# power_regulation.net
KiCad netlist of a schematic drawn in Altium Designer
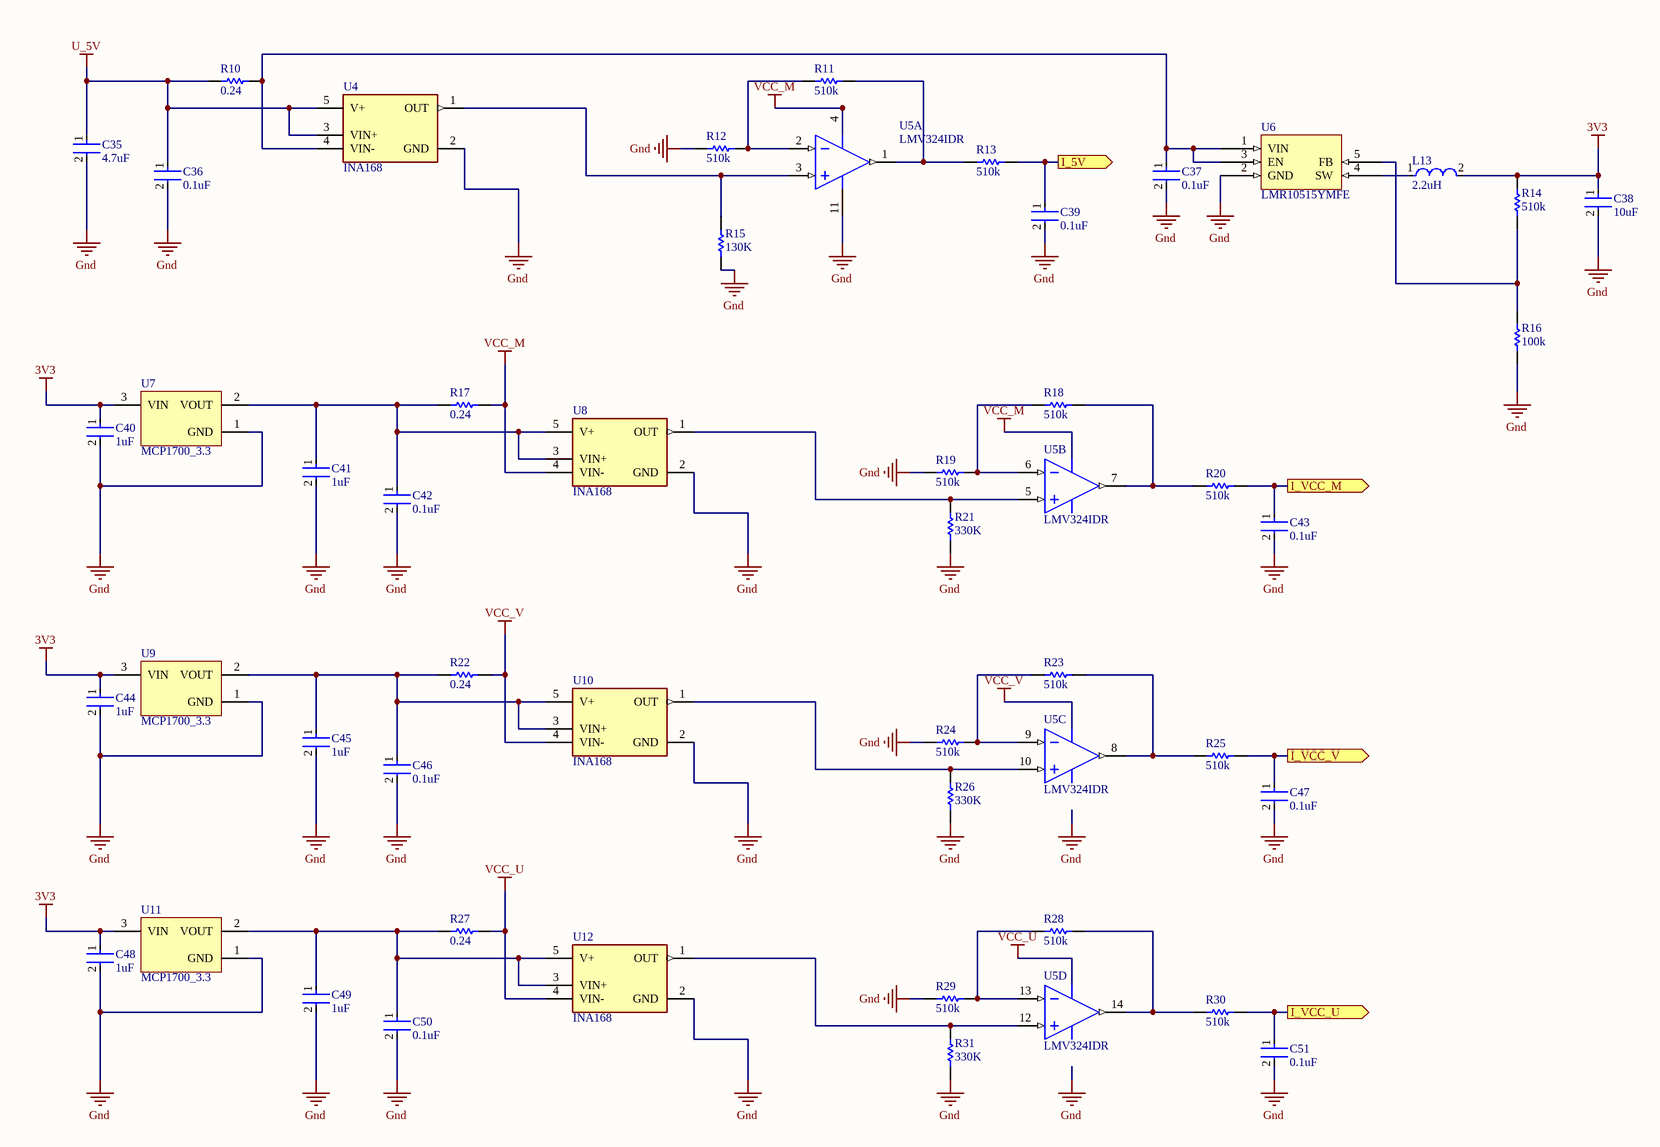
[diagram p0: power_regulation.SchDoc]

(export (version "E")
  (design (tool "Eeschema 10.0.6"))
  (components
    (comp (ref "C35")
      (value "4.7uF")
      (footprint "FP-C0805C-DN-IPC_A")
      (description "Cap Ceramic 4.7uF 25V X5R 10% SMD 0805 85°C Plastic T/R")
      (fields
        (field (name "MANUFACTURER") "KEMET")
        (field (name "MANUFACTURER PART NUMBER") "C0805C475K3PACTU")
      )
      (libsource (lib "WEST_Schematic_Library") (part "C0805C475K3PACTU"))
    )
    (comp (ref "C36")
      (value "0.1uF")
      (footprint "FP-C0805C-DN-IPC_A")
      (description "Cap Ceramic 0.1uF 50V X7R 10% SMD 2.0 x 1.2 mm 125 C Paper T/R")
      (fields
        (field (name "MANUFACTURER") "KEMET")
        (field (name "MANUFACTURER PART NUMBER") "C0805C104K5RACTU")
      )
      (libsource (lib "WEST_Schematic_Library") (part "C0805C104K5RACTU"))
    )
    (comp (ref "C37")
      (value "0.1uF")
      (footprint "FP-C0805C-DN-IPC_A")
      (description "Cap Ceramic 0.1uF 50V X7R 10% SMD 2.0 x 1.2 mm 125 C Paper T/R")
      (fields
        (field (name "MANUFACTURER") "KEMET")
        (field (name "MANUFACTURER PART NUMBER") "C0805C104K5RACTU")
      )
      (libsource (lib "WEST_Schematic_Library") (part "C0805C104K5RACTU"))
    )
    (comp (ref "C38")
      (value "10uF")
      (footprint "FP-C0805C-DN-IPC_A")
      (description "贴片电容（MLCC） 10μF ±10% 16V X5R 0805")
      (fields
        (field (name "MANUFACTURER") "Murata")
        (field (name "MANUFACTURER PART NUMBER") "GRM21BR61C106KE15L")
      )
      (libsource (lib "WEST_Schematic_Library") (part "GRM21BR61C106KE15L"))
    )
    (comp (ref "C39")
      (value "0.1uF")
      (footprint "FP-C0805C-DN-IPC_A")
      (description "Cap Ceramic 0.1uF 50V X7R 10% SMD 2.0 x 1.2 mm 125 C Paper T/R")
      (fields
        (field (name "MANUFACTURER") "KEMET")
        (field (name "MANUFACTURER PART NUMBER") "C0805C104K5RACTU")
      )
      (libsource (lib "WEST_Schematic_Library") (part "C0805C104K5RACTU"))
    )
    (comp (ref "C40")
      (value "1uF")
      (footprint "FP-C0805C-DN-IPC_A")
      (description "Cap Ceramic 1uF 16V X5R 10% SMD 0805 85C Plastic T/R")
      (fields
        (field (name "MANUFACTURER") "KEMET")
        (field (name "MANUFACTURER PART NUMBER") "C0805C105K4PACTU")
      )
      (libsource (lib "WEST_Schematic_Library") (part "C0805C105K4PACTU"))
    )
    (comp (ref "C41")
      (value "1uF")
      (footprint "FP-C0805C-DN-IPC_A")
      (description "Cap Ceramic 1uF 16V X5R 10% SMD 0805 85C Plastic T/R")
      (fields
        (field (name "MANUFACTURER") "KEMET")
        (field (name "MANUFACTURER PART NUMBER") "C0805C105K4PACTU")
      )
      (libsource (lib "WEST_Schematic_Library") (part "C0805C105K4PACTU"))
    )
    (comp (ref "C42")
      (value "0.1uF")
      (footprint "FP-C0805C-DN-IPC_A")
      (description "Cap Ceramic 0.1uF 50V X7R 10% SMD 2.0 x 1.2 mm 125 C Paper T/R")
      (fields
        (field (name "MANUFACTURER") "KEMET")
        (field (name "MANUFACTURER PART NUMBER") "C0805C104K5RACTU")
      )
      (libsource (lib "WEST_Schematic_Library") (part "C0805C104K5RACTU"))
    )
    (comp (ref "C43")
      (value "0.1uF")
      (footprint "FP-C0805C-DN-IPC_A")
      (description "Cap Ceramic 0.1uF 50V X7R 10% SMD 2.0 x 1.2 mm 125 C Paper T/R")
      (fields
        (field (name "MANUFACTURER") "KEMET")
        (field (name "MANUFACTURER PART NUMBER") "C0805C104K5RACTU")
      )
      (libsource (lib "WEST_Schematic_Library") (part "C0805C104K5RACTU"))
    )
    (comp (ref "C44")
      (value "1uF")
      (footprint "FP-C0805C-DN-IPC_A")
      (description "Cap Ceramic 1uF 16V X5R 10% SMD 0805 85C Plastic T/R")
      (fields
        (field (name "MANUFACTURER") "KEMET")
        (field (name "MANUFACTURER PART NUMBER") "C0805C105K4PACTU")
      )
      (libsource (lib "WEST_Schematic_Library") (part "C0805C105K4PACTU"))
    )
    (comp (ref "C45")
      (value "1uF")
      (footprint "FP-C0805C-DN-IPC_A")
      (description "Cap Ceramic 1uF 16V X5R 10% SMD 0805 85C Plastic T/R")
      (fields
        (field (name "MANUFACTURER") "KEMET")
        (field (name "MANUFACTURER PART NUMBER") "C0805C105K4PACTU")
      )
      (libsource (lib "WEST_Schematic_Library") (part "C0805C105K4PACTU"))
    )
    (comp (ref "C46")
      (value "0.1uF")
      (footprint "FP-C0805C-DN-IPC_A")
      (description "Cap Ceramic 0.1uF 50V X7R 10% SMD 2.0 x 1.2 mm 125 C Paper T/R")
      (fields
        (field (name "MANUFACTURER") "KEMET")
        (field (name "MANUFACTURER PART NUMBER") "C0805C104K5RACTU")
      )
      (libsource (lib "WEST_Schematic_Library") (part "C0805C104K5RACTU"))
    )
    (comp (ref "C47")
      (value "0.1uF")
      (footprint "FP-C0805C-DN-IPC_A")
      (description "Cap Ceramic 0.1uF 50V X7R 10% SMD 2.0 x 1.2 mm 125 C Paper T/R")
      (fields
        (field (name "MANUFACTURER") "KEMET")
        (field (name "MANUFACTURER PART NUMBER") "C0805C104K5RACTU")
      )
      (libsource (lib "WEST_Schematic_Library") (part "C0805C104K5RACTU"))
    )
    (comp (ref "C48")
      (value "1uF")
      (footprint "FP-C0805C-DN-IPC_A")
      (description "Cap Ceramic 1uF 16V X5R 10% SMD 0805 85C Plastic T/R")
      (fields
        (field (name "MANUFACTURER") "KEMET")
        (field (name "MANUFACTURER PART NUMBER") "C0805C105K4PACTU")
      )
      (libsource (lib "WEST_Schematic_Library") (part "C0805C105K4PACTU"))
    )
    (comp (ref "C49")
      (value "1uF")
      (footprint "FP-C0805C-DN-IPC_A")
      (description "Cap Ceramic 1uF 16V X5R 10% SMD 0805 85C Plastic T/R")
      (fields
        (field (name "MANUFACTURER") "KEMET")
        (field (name "MANUFACTURER PART NUMBER") "C0805C105K4PACTU")
      )
      (libsource (lib "WEST_Schematic_Library") (part "C0805C105K4PACTU"))
    )
    (comp (ref "C50")
      (value "0.1uF")
      (footprint "FP-C0805C-DN-IPC_A")
      (description "Cap Ceramic 0.1uF 50V X7R 10% SMD 2.0 x 1.2 mm 125 C Paper T/R")
      (fields
        (field (name "MANUFACTURER") "KEMET")
        (field (name "MANUFACTURER PART NUMBER") "C0805C104K5RACTU")
      )
      (libsource (lib "WEST_Schematic_Library") (part "C0805C104K5RACTU"))
    )
    (comp (ref "C51")
      (value "0.1uF")
      (footprint "FP-C0805C-DN-IPC_A")
      (description "Cap Ceramic 0.1uF 50V X7R 10% SMD 2.0 x 1.2 mm 125 C Paper T/R")
      (fields
        (field (name "MANUFACTURER") "KEMET")
        (field (name "MANUFACTURER PART NUMBER") "C0805C104K5RACTU")
      )
      (libsource (lib "WEST_Schematic_Library") (part "C0805C104K5RACTU"))
    )
    (comp (ref "L13")
      (value "2.2uH")
      (footprint "FP-C0805C-DN-IPC_A")
      (description "0805 2.2uH ±20% DCR=340mΩ 600mA SRF=50MHz")
      (fields
        (field (name "MANUFACTURER") "Murata")
        (field (name "MANUFACTURER PART NUMBER") "LQM21PN2R2MC0D")
      )
      (libsource (lib "WEST_Schematic_Library") (part "LQM21PN2R2MC0D"))
    )
    (comp (ref "R10")
      (value "0.24")
      (footprint "FP-C0805C-DN-IPC_A")
      (description "Res Thin Film 0805 0.24 Ohm 1% 0.33W(1/3W) 0ppm/C to 200ppm/C Pad SMD Automotive T/R")
      (fields
        (field (name "MANUFACTURER") "Susumu")
        (field (name "MANUFACTURER PART NUMBER") "RL1220S-R24-F")
      )
      (libsource (lib "WEST_Schematic_Library") (part "RL1220S-R24-F"))
    )
    (comp (ref "R11")
      (value "510k")
      (footprint "FP-C0805C-DN-IPC_A")
      (description "贴片电阻 510KΩ ±1% 1/8W ±100ppm/℃ 0805")
      (fields
        (field (name "MANUFACTURER") "Panasonic")
        (field (name "MANUFACTURER PART NUMBER") "ERJ6ENF5103V")
      )
      (libsource (lib "WEST_Schematic_Library") (part "ERJ6ENF5103V"))
    )
    (comp (ref "R12")
      (value "510k")
      (footprint "FP-C0805C-DN-IPC_A")
      (description "贴片电阻 510KΩ ±1% 1/8W ±100ppm/℃ 0805")
      (fields
        (field (name "MANUFACTURER") "Panasonic")
        (field (name "MANUFACTURER PART NUMBER") "ERJ6ENF5103V")
      )
      (libsource (lib "WEST_Schematic_Library") (part "ERJ6ENF5103V"))
    )
    (comp (ref "R13")
      (value "510k")
      (footprint "FP-C0805C-DN-IPC_A")
      (description "贴片电阻 510KΩ ±1% 1/8W ±100ppm/℃ 0805")
      (fields
        (field (name "MANUFACTURER") "Panasonic")
        (field (name "MANUFACTURER PART NUMBER") "ERJ6ENF5103V")
      )
      (libsource (lib "WEST_Schematic_Library") (part "ERJ6ENF5103V"))
    )
    (comp (ref "R14")
      (value "510k")
      (footprint "FP-C0805C-DN-IPC_A")
      (description "贴片电阻 510KΩ ±1% 1/8W ±100ppm/℃ 0805")
      (fields
        (field (name "MANUFACTURER") "Panasonic")
        (field (name "MANUFACTURER PART NUMBER") "ERJ6ENF5103V")
      )
      (libsource (lib "WEST_Schematic_Library") (part "ERJ6ENF5103V"))
    )
    (comp (ref "R15")
      (value "130K")
      (footprint "FP-C0805C-DN-IPC_A")
      (description "Res Thin Film 0805 130K Ohm 0.1% 1/8W ±25ppm/°C Molded SMD SMD Punched Carrier T/R")
      (fields
        (field (name "MANUFACTURER") "Panasonic")
        (field (name "MANUFACTURER PART NUMBER") "ERA-6AEB134V")
      )
      (libsource (lib "WEST_Schematic_Library") (part "ERA-6AEB134V"))
    )
    (comp (ref "R16")
      (value "100k")
      (footprint "FP-C0805C-DN-IPC_A")
      (description "贴片电阻 100000Ω ± 1.00% 0.125W ± 100ppm/℃ 0805")
      (fields
        (field (name "MANUFACTURER") "Yageo")
        (field (name "MANUFACTURER PART NUMBER") "RC0805FR-07100KL")
      )
      (libsource (lib "WEST_Schematic_Library") (part "RC0805FR-07100KL"))
    )
    (comp (ref "R17")
      (value "0.24")
      (footprint "FP-C0805C-DN-IPC_A")
      (description "Res Thin Film 0805 0.24 Ohm 1% 0.33W(1/3W) 0ppm/C to 200ppm/C Pad SMD Automotive T/R")
      (fields
        (field (name "MANUFACTURER") "Susumu")
        (field (name "MANUFACTURER PART NUMBER") "RL1220S-R24-F")
      )
      (libsource (lib "WEST_Schematic_Library") (part "RL1220S-R24-F"))
    )
    (comp (ref "R18")
      (value "510k")
      (footprint "FP-C0805C-DN-IPC_A")
      (description "贴片电阻 510KΩ ±1% 1/8W ±100ppm/℃ 0805")
      (fields
        (field (name "MANUFACTURER") "Panasonic")
        (field (name "MANUFACTURER PART NUMBER") "ERJ6ENF5103V")
      )
      (libsource (lib "WEST_Schematic_Library") (part "ERJ6ENF5103V"))
    )
    (comp (ref "R19")
      (value "510k")
      (footprint "FP-C0805C-DN-IPC_A")
      (description "贴片电阻 510KΩ ±1% 1/8W ±100ppm/℃ 0805")
      (fields
        (field (name "MANUFACTURER") "Panasonic")
        (field (name "MANUFACTURER PART NUMBER") "ERJ6ENF5103V")
      )
      (libsource (lib "WEST_Schematic_Library") (part "ERJ6ENF5103V"))
    )
    (comp (ref "R20")
      (value "510k")
      (footprint "FP-C0805C-DN-IPC_A")
      (description "贴片电阻 510KΩ ±1% 1/8W ±100ppm/℃ 0805")
      (fields
        (field (name "MANUFACTURER") "Panasonic")
        (field (name "MANUFACTURER PART NUMBER") "ERJ6ENF5103V")
      )
      (libsource (lib "WEST_Schematic_Library") (part "ERJ6ENF5103V"))
    )
    (comp (ref "R21")
      (value "330K")
      (footprint "FP-C0805C-DN-IPC_A")
      (description "Res Thick Film 0805 330K Ohm 5% 1/8W ±200ppm/°C Molded SMD SMD Paper T/R")
      (fields
        (field (name "MANUFACTURER") "Vishay Dale")
        (field (name "MANUFACTURER PART NUMBER") "CRCW0805330KJNEA")
      )
      (libsource (lib "WEST_Schematic_Library") (part "CRCW0805330KJNEA"))
    )
    (comp (ref "R22")
      (value "0.24")
      (footprint "FP-C0805C-DN-IPC_A")
      (description "Res Thin Film 0805 0.24 Ohm 1% 0.33W(1/3W) 0ppm/C to 200ppm/C Pad SMD Automotive T/R")
      (fields
        (field (name "MANUFACTURER") "Susumu")
        (field (name "MANUFACTURER PART NUMBER") "RL1220S-R24-F")
      )
      (libsource (lib "WEST_Schematic_Library") (part "RL1220S-R24-F"))
    )
    (comp (ref "R23")
      (value "510k")
      (footprint "FP-C0805C-DN-IPC_A")
      (description "贴片电阻 510KΩ ±1% 1/8W ±100ppm/℃ 0805")
      (fields
        (field (name "MANUFACTURER") "Panasonic")
        (field (name "MANUFACTURER PART NUMBER") "ERJ6ENF5103V")
      )
      (libsource (lib "WEST_Schematic_Library") (part "ERJ6ENF5103V"))
    )
    (comp (ref "R24")
      (value "510k")
      (footprint "FP-C0805C-DN-IPC_A")
      (description "贴片电阻 510KΩ ±1% 1/8W ±100ppm/℃ 0805")
      (fields
        (field (name "MANUFACTURER") "Panasonic")
        (field (name "MANUFACTURER PART NUMBER") "ERJ6ENF5103V")
      )
      (libsource (lib "WEST_Schematic_Library") (part "ERJ6ENF5103V"))
    )
    (comp (ref "R25")
      (value "510k")
      (footprint "FP-C0805C-DN-IPC_A")
      (description "贴片电阻 510KΩ ±1% 1/8W ±100ppm/℃ 0805")
      (fields
        (field (name "MANUFACTURER") "Panasonic")
        (field (name "MANUFACTURER PART NUMBER") "ERJ6ENF5103V")
      )
      (libsource (lib "WEST_Schematic_Library") (part "ERJ6ENF5103V"))
    )
    (comp (ref "R26")
      (value "330K")
      (footprint "FP-C0805C-DN-IPC_A")
      (description "Res Thick Film 0805 330K Ohm 5% 1/8W ±200ppm/°C Molded SMD SMD Paper T/R")
      (fields
        (field (name "MANUFACTURER") "Vishay Dale")
        (field (name "MANUFACTURER PART NUMBER") "CRCW0805330KJNEA")
      )
      (libsource (lib "WEST_Schematic_Library") (part "CRCW0805330KJNEA"))
    )
    (comp (ref "R27")
      (value "0.24")
      (footprint "FP-C0805C-DN-IPC_A")
      (description "Res Thin Film 0805 0.24 Ohm 1% 0.33W(1/3W) 0ppm/C to 200ppm/C Pad SMD Automotive T/R")
      (fields
        (field (name "MANUFACTURER") "Susumu")
        (field (name "MANUFACTURER PART NUMBER") "RL1220S-R24-F")
      )
      (libsource (lib "WEST_Schematic_Library") (part "RL1220S-R24-F"))
    )
    (comp (ref "R28")
      (value "510k")
      (footprint "FP-C0805C-DN-IPC_A")
      (description "贴片电阻 510KΩ ±1% 1/8W ±100ppm/℃ 0805")
      (fields
        (field (name "MANUFACTURER") "Panasonic")
        (field (name "MANUFACTURER PART NUMBER") "ERJ6ENF5103V")
      )
      (libsource (lib "WEST_Schematic_Library") (part "ERJ6ENF5103V"))
    )
    (comp (ref "R29")
      (value "510k")
      (footprint "FP-C0805C-DN-IPC_A")
      (description "贴片电阻 510KΩ ±1% 1/8W ±100ppm/℃ 0805")
      (fields
        (field (name "MANUFACTURER") "Panasonic")
        (field (name "MANUFACTURER PART NUMBER") "ERJ6ENF5103V")
      )
      (libsource (lib "WEST_Schematic_Library") (part "ERJ6ENF5103V"))
    )
    (comp (ref "R30")
      (value "510k")
      (footprint "FP-C0805C-DN-IPC_A")
      (description "贴片电阻 510KΩ ±1% 1/8W ±100ppm/℃ 0805")
      (fields
        (field (name "MANUFACTURER") "Panasonic")
        (field (name "MANUFACTURER PART NUMBER") "ERJ6ENF5103V")
      )
      (libsource (lib "WEST_Schematic_Library") (part "ERJ6ENF5103V"))
    )
    (comp (ref "R31")
      (value "330K")
      (footprint "FP-C0805C-DN-IPC_A")
      (description "Res Thick Film 0805 330K Ohm 5% 1/8W ±200ppm/°C Molded SMD SMD Paper T/R")
      (fields
        (field (name "MANUFACTURER") "Vishay Dale")
        (field (name "MANUFACTURER PART NUMBER") "CRCW0805330KJNEA")
      )
      (libsource (lib "WEST_Schematic_Library") (part "CRCW0805330KJNEA"))
    )
    (comp (ref "U4")
      (value "INA168")
      (footprint "FP-DBV0005A-IPC_A")
      (description "AEC-Q100, 2.7 to 60V, 800kHz Variable gain current sense amplifier 8-TSSOP -40 to 125")
      (fields
        (field (name "MANUFACTURER") "Texas Instruments")
        (field (name "MANUFACTURER PART NUMBER") "INA168QPWRQ1")
      )
      (libsource (lib "WEST_Schematic_Library") (part "INA168QPWRQ1"))
    )
    (comp (ref "U5")
      (value "LMV324IDR")
      (footprint "D0014A_V")
      (description "IC OPAMP GP 1MHZ RRO 14SOIC")
      (fields (field (name "MANUFACTURER") "Texas Instruments"))
      (libsource (lib "WEST_Schematic_Library") (part "LMV324IDR"))
    )
    (comp (ref "U6")
      (value "LMR10515YMFE")
      (footprint "SOT95P245X145-5N")
      (description "5.5Vin, 1.5A Step-Down Voltage Regulator in SOT-23 and LLP 5-SOT-23 -40 to 125")
      (fields
        (field (name "MANUFACTURER") "TI National Semiconductor")
        (field (name "MANUFACTURER PART NUMBER") "LMR10515YMFE/NOPB")
      )
      (libsource (lib "WEST_Schematic_Library") (part "LMR10515YMFE/NOPB"))
    )
    (comp (ref "U7")
      (value "MCP1700_3.3")
      (footprint "SOT-23-TT3_L")
      (description "IC REG LDO 3.3V 0.25A SOT23-3")
      (fields
        (field (name "MANUFACTURER") "Microchip")
        (field (name "MANUFACTURER PART NUMBER") "MCP1700T-3302E/TT")
      )
      (libsource (lib "WEST_Schematic_Library") (part "MCP1700T-3302E/TT"))
    )
    (comp (ref "U8")
      (value "INA168")
      (footprint "FP-DBV0005A-IPC_A")
      (description "AEC-Q100, 2.7 to 60V, 800kHz Variable gain current sense amplifier 8-TSSOP -40 to 125")
      (fields
        (field (name "MANUFACTURER") "Texas Instruments")
        (field (name "MANUFACTURER PART NUMBER") "INA168QPWRQ1")
      )
      (libsource (lib "WEST_Schematic_Library") (part "INA168QPWRQ1"))
    )
    (comp (ref "U9")
      (value "MCP1700_3.3")
      (footprint "SOT-23-TT3_L")
      (description "IC REG LDO 3.3V 0.25A SOT23-3")
      (fields
        (field (name "MANUFACTURER") "Microchip")
        (field (name "MANUFACTURER PART NUMBER") "MCP1700T-3302E/TT")
      )
      (libsource (lib "WEST_Schematic_Library") (part "MCP1700T-3302E/TT"))
    )
    (comp (ref "U10")
      (value "INA168")
      (footprint "FP-DBV0005A-IPC_A")
      (description "AEC-Q100, 2.7 to 60V, 800kHz Variable gain current sense amplifier 8-TSSOP -40 to 125")
      (fields
        (field (name "MANUFACTURER") "Texas Instruments")
        (field (name "MANUFACTURER PART NUMBER") "INA168QPWRQ1")
      )
      (libsource (lib "WEST_Schematic_Library") (part "INA168QPWRQ1"))
    )
    (comp (ref "U11")
      (value "MCP1700_3.3")
      (footprint "SOT-23-TT3_L")
      (description "IC REG LDO 3.3V 0.25A SOT23-3")
      (fields
        (field (name "MANUFACTURER") "Microchip")
        (field (name "MANUFACTURER PART NUMBER") "MCP1700T-3302E/TT")
      )
      (libsource (lib "WEST_Schematic_Library") (part "MCP1700T-3302E/TT"))
    )
    (comp (ref "U12")
      (value "INA168")
      (footprint "FP-DBV0005A-IPC_A")
      (description "AEC-Q100, 2.7 to 60V, 800kHz Variable gain current sense amplifier 8-TSSOP -40 to 125")
      (fields
        (field (name "MANUFACTURER") "Texas Instruments")
        (field (name "MANUFACTURER PART NUMBER") "INA168QPWRQ1")
      )
      (libsource (lib "WEST_Schematic_Library") (part "INA168QPWRQ1"))
    )
  )
  (nets
    (net (code "1") (name "/I_5V") (class "Default")
      (node (ref "C39") (pin "1") (pinfunction "1_1") (pintype "passive"))
      (node (ref "R13") (pin "1") (pinfunction "1_1") (pintype "passive"))
    )
    (net (code "2") (name "/I_VCC_M") (class "Default")
      (node (ref "C43") (pin "1") (pinfunction "1_1") (pintype "passive"))
      (node (ref "R20") (pin "1") (pinfunction "1_1") (pintype "passive"))
    )
    (net (code "3") (name "/I_VCC_U") (class "Default")
      (node (ref "C51") (pin "1") (pinfunction "1_1") (pintype "passive"))
      (node (ref "R30") (pin "1") (pinfunction "1_1") (pintype "passive"))
    )
    (net (code "4") (name "/I_VCC_V") (class "Default")
      (node (ref "C47") (pin "1") (pinfunction "1_1") (pintype "passive"))
      (node (ref "R25") (pin "1") (pinfunction "1_1") (pintype "passive"))
    )
    (net (code "5") (name "3V3") (class "Default")
      (node (ref "C38") (pin "1") (pinfunction "1_1") (pintype "passive"))
      (node (ref "C40") (pin "1") (pinfunction "1_1") (pintype "passive"))
      (node (ref "C44") (pin "1") (pinfunction "1_1") (pintype "passive"))
      (node (ref "C48") (pin "1") (pinfunction "1_1") (pintype "passive"))
      (node (ref "L13") (pin "2") (pinfunction "2_2") (pintype "passive"))
      (node (ref "R14") (pin "2") (pinfunction "2_2") (pintype "passive"))
      (node (ref "U11") (pin "3") (pinfunction "VIN_3") (pintype "power_in"))
      (node (ref "U7") (pin "3") (pinfunction "VIN_3") (pintype "power_in"))
      (node (ref "U9") (pin "3") (pinfunction "VIN_3") (pintype "power_in"))
    )
    (net (code "6") (name "Gnd") (class "Default")
      (node (ref "C35") (pin "2") (pinfunction "2_2") (pintype "passive"))
      (node (ref "C36") (pin "2") (pinfunction "2_2") (pintype "passive"))
      (node (ref "C37") (pin "2") (pinfunction "2_2") (pintype "passive"))
      (node (ref "C38") (pin "2") (pinfunction "2_2") (pintype "passive"))
      (node (ref "C39") (pin "2") (pinfunction "2_2") (pintype "passive"))
      (node (ref "C40") (pin "2") (pinfunction "2_2") (pintype "passive"))
      (node (ref "C41") (pin "2") (pinfunction "2_2") (pintype "passive"))
      (node (ref "C42") (pin "2") (pinfunction "2_2") (pintype "passive"))
      (node (ref "C43") (pin "2") (pinfunction "2_2") (pintype "passive"))
      (node (ref "C44") (pin "2") (pinfunction "2_2") (pintype "passive"))
      (node (ref "C45") (pin "2") (pinfunction "2_2") (pintype "passive"))
      (node (ref "C46") (pin "2") (pinfunction "2_2") (pintype "passive"))
      (node (ref "C47") (pin "2") (pinfunction "2_2") (pintype "passive"))
      (node (ref "C48") (pin "2") (pinfunction "2_2") (pintype "passive"))
      (node (ref "C49") (pin "2") (pinfunction "2_2") (pintype "passive"))
      (node (ref "C50") (pin "2") (pinfunction "2_2") (pintype "passive"))
      (node (ref "C51") (pin "2") (pinfunction "2_2") (pintype "passive"))
      (node (ref "R12") (pin "2") (pinfunction "2_2") (pintype "passive"))
      (node (ref "R15") (pin "1") (pinfunction "1_1") (pintype "passive"))
      (node (ref "R16") (pin "1") (pinfunction "1_1") (pintype "passive"))
      (node (ref "R19") (pin "2") (pinfunction "2_2") (pintype "passive"))
      (node (ref "R21") (pin "1") (pinfunction "1_1") (pintype "passive"))
      (node (ref "R24") (pin "2") (pinfunction "2_2") (pintype "passive"))
      (node (ref "R26") (pin "1") (pinfunction "1_1") (pintype "passive"))
      (node (ref "R29") (pin "2") (pinfunction "2_2") (pintype "passive"))
      (node (ref "R31") (pin "1") (pinfunction "1_1") (pintype "passive"))
      (node (ref "U10") (pin "2") (pinfunction "GND_2") (pintype "power_in"))
      (node (ref "U11") (pin "1") (pinfunction "GND_1") (pintype "power_in"))
      (node (ref "U12") (pin "2") (pinfunction "GND_2") (pintype "power_in"))
      (node (ref "U4") (pin "2") (pinfunction "GND_2") (pintype "power_in"))
      (node (ref "U5") (pin "11") (pinfunction "GND_11") (pintype "power_in"))
      (node (ref "U6") (pin "2") (pinfunction "GND_2") (pintype "input"))
      (node (ref "U7") (pin "1") (pinfunction "GND_1") (pintype "power_in"))
      (node (ref "U8") (pin "2") (pinfunction "GND_2") (pintype "power_in"))
      (node (ref "U9") (pin "1") (pinfunction "GND_1") (pintype "power_in"))
    )
    (net (code "7") (name "Net-(U4-OUT)") (class "Default")
      (node (ref "R15") (pin "2") (pinfunction "2_2") (pintype "passive"))
      (node (ref "U4") (pin "1") (pinfunction "OUT_1") (pintype "output"))
      (node (ref "U5") (pin "3") (pinfunction "1IN+_3") (pintype "input"))
    )
    (net (code "8") (name "Net-(U4-VIN-)") (class "Default")
      (node (ref "C37") (pin "1") (pinfunction "1_1") (pintype "passive"))
      (node (ref "R10") (pin "2") (pinfunction "2_2") (pintype "passive"))
      (node (ref "U4") (pin "4") (pinfunction "VIN-_4") (pintype "power_in"))
      (node (ref "U6") (pin "1") (pinfunction "VIN_1") (pintype "input"))
      (node (ref "U6") (pin "3") (pinfunction "EN_3") (pintype "input"))
    )
    (net (code "9") (name "Net-(U5A-1IN-)") (class "Default")
      (node (ref "R11") (pin "2") (pinfunction "2_2") (pintype "passive"))
      (node (ref "R12") (pin "1") (pinfunction "1_1") (pintype "passive"))
      (node (ref "U5") (pin "2") (pinfunction "1IN-_2") (pintype "input"))
    )
    (net (code "10") (name "Net-(U5A-1OUT)") (class "Default")
      (node (ref "R11") (pin "1") (pinfunction "1_1") (pintype "passive"))
      (node (ref "R13") (pin "2") (pinfunction "2_2") (pintype "passive"))
      (node (ref "U5") (pin "1") (pinfunction "1OUT_1") (pintype "output"))
    )
    (net (code "11") (name "Net-(U5B-1IN+)") (class "Default")
      (node (ref "R21") (pin "2") (pinfunction "2_2") (pintype "passive"))
      (node (ref "U5") (pin "5") (pinfunction "1IN+_5") (pintype "input"))
      (node (ref "U8") (pin "1") (pinfunction "OUT_1") (pintype "output"))
    )
    (net (code "12") (name "Net-(U5B-1IN-)") (class "Default")
      (node (ref "R18") (pin "2") (pinfunction "2_2") (pintype "passive"))
      (node (ref "R19") (pin "1") (pinfunction "1_1") (pintype "passive"))
      (node (ref "U5") (pin "6") (pinfunction "1IN-_6") (pintype "input"))
    )
    (net (code "13") (name "Net-(U5B-1OUT)") (class "Default")
      (node (ref "R18") (pin "1") (pinfunction "1_1") (pintype "passive"))
      (node (ref "R20") (pin "2") (pinfunction "2_2") (pintype "passive"))
      (node (ref "U5") (pin "7") (pinfunction "1OUT_7") (pintype "output"))
    )
    (net (code "14") (name "Net-(U5C-1IN-)") (class "Default")
      (node (ref "R23") (pin "2") (pinfunction "2_2") (pintype "passive"))
      (node (ref "R24") (pin "1") (pinfunction "1_1") (pintype "passive"))
      (node (ref "U5") (pin "9") (pinfunction "1IN-_9") (pintype "input"))
    )
    (net (code "15") (name "Net-(U5C-1OUT)") (class "Default")
      (node (ref "R23") (pin "1") (pinfunction "1_1") (pintype "passive"))
      (node (ref "R25") (pin "2") (pinfunction "2_2") (pintype "passive"))
      (node (ref "U5") (pin "8") (pinfunction "1OUT_8") (pintype "output"))
    )
    (net (code "16") (name "Net-(U5D-1IN-)") (class "Default")
      (node (ref "R28") (pin "2") (pinfunction "2_2") (pintype "passive"))
      (node (ref "R29") (pin "1") (pinfunction "1_1") (pintype "passive"))
      (node (ref "U5") (pin "13") (pinfunction "1IN-_13") (pintype "input"))
    )
    (net (code "17") (name "Net-(U5D-1OUT)") (class "Default")
      (node (ref "R28") (pin "1") (pinfunction "1_1") (pintype "passive"))
      (node (ref "R30") (pin "2") (pinfunction "2_2") (pintype "passive"))
      (node (ref "U5") (pin "14") (pinfunction "1OUT_14") (pintype "output"))
    )
    (net (code "18") (name "Net-(U6-FB)") (class "Default")
      (node (ref "R14") (pin "1") (pinfunction "1_1") (pintype "passive"))
      (node (ref "R16") (pin "2") (pinfunction "2_2") (pintype "passive"))
      (node (ref "U6") (pin "5") (pinfunction "FB_5") (pintype "input"))
    )
    (net (code "19") (name "Net-(U6-SW)") (class "Default")
      (node (ref "L13") (pin "1") (pinfunction "1_1") (pintype "passive"))
      (node (ref "U6") (pin "4") (pinfunction "SW_4") (pintype "input"))
    )
    (net (code "20") (name "Net-(U7-VOUT)") (class "Default")
      (node (ref "C41") (pin "1") (pinfunction "1_1") (pintype "passive"))
      (node (ref "C42") (pin "1") (pinfunction "1_1") (pintype "passive"))
      (node (ref "R17") (pin "1") (pinfunction "1_1") (pintype "passive"))
      (node (ref "U7") (pin "2") (pinfunction "VOUT_2") (pintype "power_in"))
      (node (ref "U8") (pin "3") (pinfunction "VIN+_3") (pintype "power_in"))
      (node (ref "U8") (pin "5") (pinfunction "V+_5") (pintype "power_in"))
    )
    (net (code "21") (name "Net-(U10-OUT)") (class "Default")
      (node (ref "R26") (pin "2") (pinfunction "2_2") (pintype "passive"))
      (node (ref "U10") (pin "1") (pinfunction "OUT_1") (pintype "output"))
      (node (ref "U5") (pin "10") (pinfunction "1IN+_10") (pintype "input"))
    )
    (net (code "22") (name "Net-(U10-V+)") (class "Default")
      (node (ref "C45") (pin "1") (pinfunction "1_1") (pintype "passive"))
      (node (ref "C46") (pin "1") (pinfunction "1_1") (pintype "passive"))
      (node (ref "R22") (pin "1") (pinfunction "1_1") (pintype "passive"))
      (node (ref "U10") (pin "3") (pinfunction "VIN+_3") (pintype "power_in"))
      (node (ref "U10") (pin "5") (pinfunction "V+_5") (pintype "power_in"))
      (node (ref "U9") (pin "2") (pinfunction "VOUT_2") (pintype "power_in"))
    )
    (net (code "23") (name "Net-(U11-VOUT)") (class "Default")
      (node (ref "C49") (pin "1") (pinfunction "1_1") (pintype "passive"))
      (node (ref "C50") (pin "1") (pinfunction "1_1") (pintype "passive"))
      (node (ref "R27") (pin "1") (pinfunction "1_1") (pintype "passive"))
      (node (ref "U11") (pin "2") (pinfunction "VOUT_2") (pintype "power_in"))
      (node (ref "U12") (pin "3") (pinfunction "VIN+_3") (pintype "power_in"))
      (node (ref "U12") (pin "5") (pinfunction "V+_5") (pintype "power_in"))
    )
    (net (code "24") (name "Net-(U12-OUT)") (class "Default")
      (node (ref "R31") (pin "2") (pinfunction "2_2") (pintype "passive"))
      (node (ref "U12") (pin "1") (pinfunction "OUT_1") (pintype "output"))
      (node (ref "U5") (pin "12") (pinfunction "1IN+_12") (pintype "input"))
    )
    (net (code "25") (name "U_5V") (class "Default")
      (node (ref "C35") (pin "1") (pinfunction "1_1") (pintype "passive"))
      (node (ref "C36") (pin "1") (pinfunction "1_1") (pintype "passive"))
      (node (ref "R10") (pin "1") (pinfunction "1_1") (pintype "passive"))
      (node (ref "U4") (pin "3") (pinfunction "VIN+_3") (pintype "power_in"))
      (node (ref "U4") (pin "5") (pinfunction "V+_5") (pintype "power_in"))
    )
    (net (code "26") (name "VCC_M") (class "Default")
      (node (ref "R17") (pin "2") (pinfunction "2_2") (pintype "passive"))
      (node (ref "U5") (pin "4") (pinfunction "VCC+_4") (pintype "power_in"))
      (node (ref "U8") (pin "4") (pinfunction "VIN-_4") (pintype "power_in"))
    )
    (net (code "27") (name "VCC_U") (class "Default")
      (node (ref "R27") (pin "2") (pinfunction "2_2") (pintype "passive"))
      (node (ref "U12") (pin "4") (pinfunction "VIN-_4") (pintype "power_in"))
    )
    (net (code "28") (name "VCC_V") (class "Default")
      (node (ref "R22") (pin "2") (pinfunction "2_2") (pintype "passive"))
      (node (ref "U10") (pin "4") (pinfunction "VIN-_4") (pintype "power_in"))
    )
  )
)
